# MICRO_SQUARED_SENSING_MCP1700.net
KiCad netlist of a schematic drawn in EAGLE
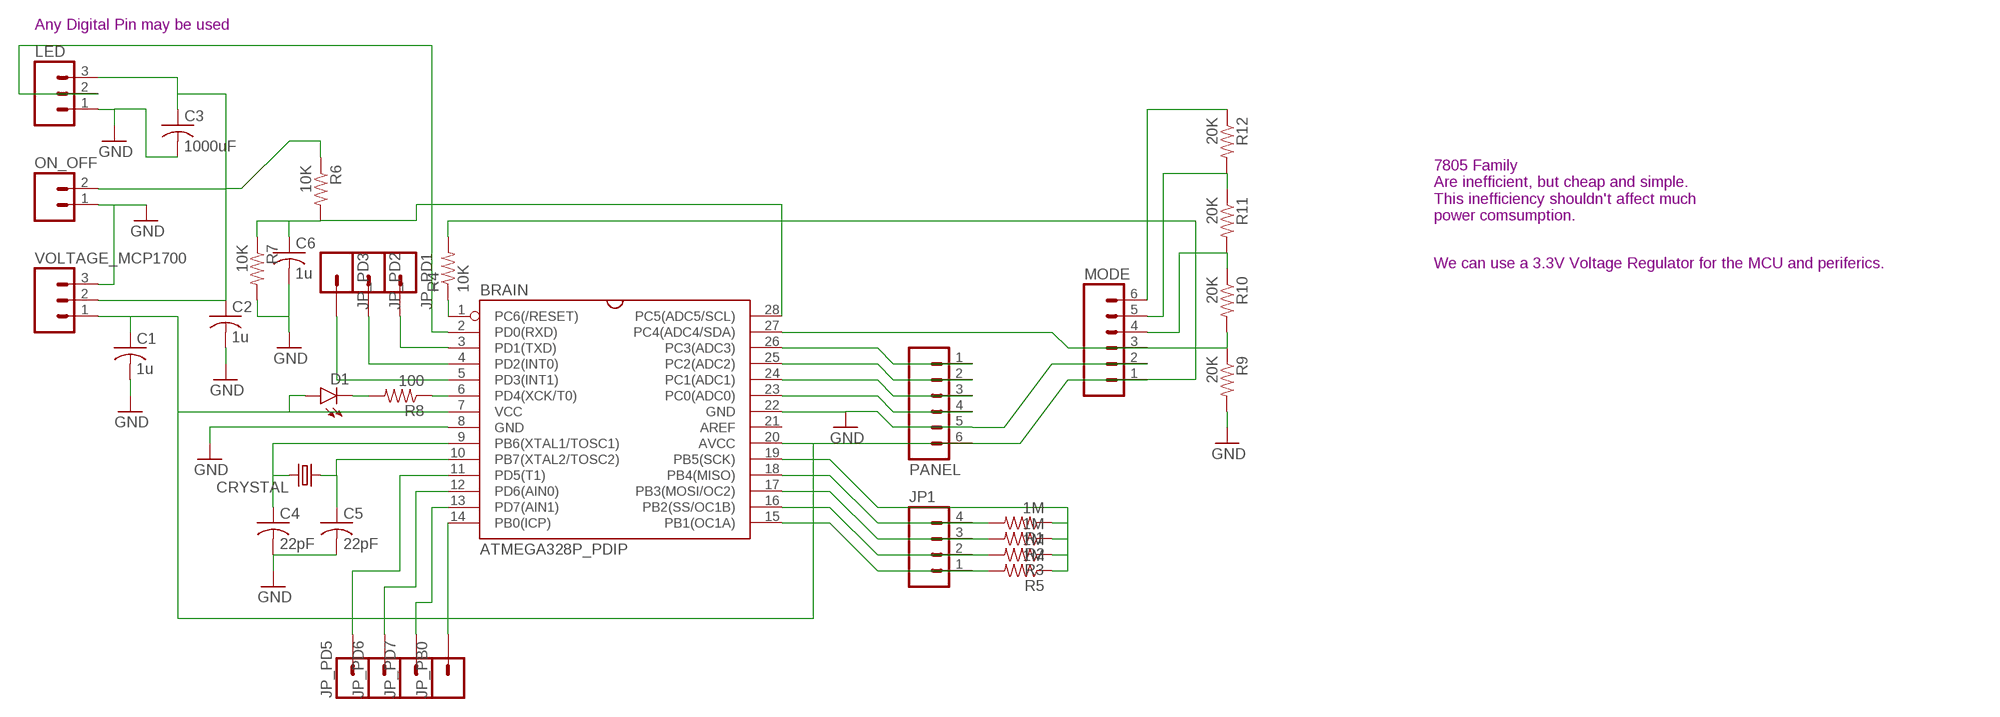
[diagram p0: schematic, sheet 1]

(export (version "E")
  (design (tool "Eeschema 10.0.6"))
  (components
    (comp (ref "BRAIN")
      (value "ATMEGA328P_PDIP")
      (footprint "eagle-import:DIL-28-3")
      (libsource (lib "eagle-import") (part "ATMEGA328P_PDIP"))
    )
    (comp (ref "C1")
      (value "1u")
      (footprint "eagle-import:C050-025X075")
      (libsource (lib "eagle-import") (part "C-US050-025X075"))
    )
    (comp (ref "C2")
      (value "1u")
      (footprint "eagle-import:C050-025X075")
      (libsource (lib "eagle-import") (part "C-US050-025X075"))
    )
    (comp (ref "C3")
      (value "1000uF")
      (footprint "eagle-import:C050-075X075")
      (libsource (lib "eagle-import") (part "C-US050-075X075"))
    )
    (comp (ref "C4")
      (value "22pF")
      (footprint "eagle-import:C025-024X044")
      (libsource (lib "eagle-import") (part "C-US025-024X044"))
    )
    (comp (ref "C5")
      (value "22pF")
      (footprint "eagle-import:C025-024X044")
      (libsource (lib "eagle-import") (part "C-US025-024X044"))
    )
    (comp (ref "C6")
      (value "1u")
      (footprint "eagle-import:C050-025X075")
      (libsource (lib "eagle-import") (part "C-US050-025X075"))
    )
    (comp (ref "CRYSTAL")
      (value "CRYSTALHC49US")
      (footprint "eagle-import:HC49US")
      (libsource (lib "eagle-import") (part "CRYSTALHC49US"))
    )
    (comp (ref "D1")
      (value "LED3MM")
      (footprint "eagle-import:LED3MM")
      (libsource (lib "eagle-import") (part "LED3MM"))
    )
    (comp (ref "JP1")
      (value "M04PTH")
      (footprint "eagle-import:1X04")
      (libsource (lib "eagle-import") (part "M04PTH"))
    )
    (comp (ref "JP_PB0")
      (value "M01PTH")
      (footprint "eagle-import:1X01")
      (libsource (lib "eagle-import") (part "M01PTH"))
    )
    (comp (ref "JP_PD1")
      (value "M01PTH")
      (footprint "eagle-import:1X01")
      (libsource (lib "eagle-import") (part "M01PTH"))
    )
    (comp (ref "JP_PD2")
      (value "M01PTH")
      (footprint "eagle-import:1X01")
      (libsource (lib "eagle-import") (part "M01PTH"))
    )
    (comp (ref "JP_PD3")
      (value "M01PTH")
      (footprint "eagle-import:1X01")
      (libsource (lib "eagle-import") (part "M01PTH"))
    )
    (comp (ref "JP_PD5")
      (value "M01PTH")
      (footprint "eagle-import:1X01")
      (libsource (lib "eagle-import") (part "M01PTH"))
    )
    (comp (ref "JP_PD6")
      (value "M01PTH")
      (footprint "eagle-import:1X01")
      (libsource (lib "eagle-import") (part "M01PTH"))
    )
    (comp (ref "JP_PD7")
      (value "M01PTH")
      (footprint "eagle-import:1X01")
      (libsource (lib "eagle-import") (part "M01PTH"))
    )
    (comp (ref "LED")
      (value "M03PTH")
      (footprint "eagle-import:1X03")
      (libsource (lib "eagle-import") (part "M03PTH"))
    )
    (comp (ref "MODE")
      (value "M06SILK_FEMALE_PTH")
      (footprint "eagle-import:1X06")
      (libsource (lib "eagle-import") (part "M06SILK_FEMALE_PTH"))
    )
    (comp (ref "ON_OFF")
      (value "M02PTH")
      (footprint "eagle-import:1X02")
      (libsource (lib "eagle-import") (part "M02PTH"))
    )
    (comp (ref "PANEL")
      (value "M06NO_SILK_FEMALE_PTH")
      (footprint "eagle-import:1X06_NO_SILK")
      (libsource (lib "eagle-import") (part "M06NO_SILK_FEMALE_PTH"))
    )
    (comp (ref "R1")
      (value "1M")
      (footprint "eagle-import:AXIAL-0.3")
      (libsource (lib "eagle-import") (part "RESISTORAXIAL-0.3"))
    )
    (comp (ref "R2")
      (value "1M")
      (footprint "eagle-import:AXIAL-0.3")
      (libsource (lib "eagle-import") (part "RESISTORAXIAL-0.3"))
    )
    (comp (ref "R3")
      (value "1M")
      (footprint "eagle-import:AXIAL-0.3")
      (libsource (lib "eagle-import") (part "RESISTORAXIAL-0.3"))
    )
    (comp (ref "R4")
      (value "10K")
      (footprint "eagle-import:AXIAL-0.3")
      (libsource (lib "eagle-import") (part "RESISTORAXIAL-0.3"))
    )
    (comp (ref "R5")
      (value "1M")
      (footprint "eagle-import:AXIAL-0.3")
      (libsource (lib "eagle-import") (part "RESISTORAXIAL-0.3"))
    )
    (comp (ref "R6")
      (value "10K")
      (footprint "eagle-import:AXIAL-0.3")
      (libsource (lib "eagle-import") (part "RESISTORAXIAL-0.3"))
    )
    (comp (ref "R7")
      (value "10K")
      (footprint "eagle-import:AXIAL-0.3")
      (libsource (lib "eagle-import") (part "RESISTORAXIAL-0.3"))
    )
    (comp (ref "R8")
      (value "100")
      (footprint "eagle-import:AXIAL-0.3")
      (libsource (lib "eagle-import") (part "RESISTORAXIAL-0.3"))
    )
    (comp (ref "R9")
      (value "20K")
      (footprint "eagle-import:AXIAL-0.3")
      (libsource (lib "eagle-import") (part "RESISTORAXIAL-0.3"))
    )
    (comp (ref "R10")
      (value "20K")
      (footprint "eagle-import:AXIAL-0.3")
      (libsource (lib "eagle-import") (part "RESISTORAXIAL-0.3"))
    )
    (comp (ref "R11")
      (value "20K")
      (footprint "eagle-import:AXIAL-0.3")
      (libsource (lib "eagle-import") (part "RESISTORAXIAL-0.3"))
    )
    (comp (ref "R12")
      (value "20K")
      (footprint "eagle-import:AXIAL-0.3")
      (libsource (lib "eagle-import") (part "RESISTORAXIAL-0.3"))
    )
    (comp (ref "VOLTAGE_MCP1700")
      (value "M03PTH")
      (footprint "eagle-import:1X03")
      (libsource (lib "eagle-import") (part "M03PTH"))
    )
  )
  (nets
    (net (code "1") (name "GND") (class "Default")
      (node (ref "BRAIN") (pin "22") (pinfunction "GND_22") (pintype "bidirectional"))
      (node (ref "BRAIN") (pin "8") (pinfunction "GND_8") (pintype "bidirectional"))
      (node (ref "C1") (pin "2") (pinfunction "2_2") (pintype "passive"))
      (node (ref "C2") (pin "2") (pinfunction "2_2") (pintype "passive"))
      (node (ref "C3") (pin "2") (pinfunction "2_2") (pintype "passive"))
      (node (ref "C4") (pin "2") (pinfunction "2_2") (pintype "passive"))
      (node (ref "C5") (pin "2") (pinfunction "2_2") (pintype "passive"))
      (node (ref "C6") (pin "2") (pinfunction "2_2") (pintype "passive"))
      (node (ref "LED") (pin "1") (pinfunction "1_1") (pintype "passive"))
      (node (ref "MODE") (pin "2") (pinfunction "2_2") (pintype "passive"))
      (node (ref "ON_OFF") (pin "1") (pinfunction "1_1") (pintype "passive"))
      (node (ref "PANEL") (pin "5") (pinfunction "5_5") (pintype "passive"))
      (node (ref "R7") (pin "P$2") (pinfunction "2_P$2") (pintype "passive"))
      (node (ref "R9") (pin "P$2") (pinfunction "2_P$2") (pintype "passive"))
      (node (ref "VOLTAGE_MCP1700") (pin "3") (pinfunction "3_3") (pintype "passive"))
    )
    (net (code "2") (name "Net-(BRAIN-AVCC)") (class "Default")
      (node (ref "BRAIN") (pin "20") (pinfunction "AVCC_20") (pintype "bidirectional"))
      (node (ref "BRAIN") (pin "7") (pinfunction "VCC_7") (pintype "bidirectional"))
      (node (ref "C1") (pin "1") (pinfunction "1_1") (pintype "passive"))
      (node (ref "D1") (pin "A") (pinfunction "A_A") (pintype "passive"))
      (node (ref "MODE") (pin "1") (pinfunction "1_1") (pintype "passive"))
      (node (ref "PANEL") (pin "6") (pinfunction "6_6") (pintype "passive"))
      (node (ref "R4") (pin "P$2") (pinfunction "2_P$2") (pintype "passive"))
      (node (ref "VOLTAGE_MCP1700") (pin "1") (pinfunction "1_1") (pintype "passive"))
    )
    (net (code "3") (name "Net-(BRAIN-PB0(ICP))") (class "Default")
      (node (ref "BRAIN") (pin "14") (pinfunction "PB0(ICP)_14") (pintype "bidirectional"))
      (node (ref "JP_PB0") (pin "1") (pinfunction "1_1") (pintype "passive"))
    )
    (net (code "4") (name "Net-(BRAIN-PB1(OC1A))") (class "Default")
      (node (ref "BRAIN") (pin "15") (pinfunction "PB1(OC1A)_15") (pintype "bidirectional"))
      (node (ref "JP1") (pin "1") (pinfunction "1_1") (pintype "passive"))
      (node (ref "R5") (pin "P$2") (pinfunction "2_P$2") (pintype "passive"))
    )
    (net (code "5") (name "Net-(BRAIN-PB2(SS{slash}OC1B))") (class "Default")
      (node (ref "BRAIN") (pin "16") (pinfunction "PB2(SS/OC1B)_16") (pintype "bidirectional"))
      (node (ref "JP1") (pin "2") (pinfunction "2_2") (pintype "passive"))
      (node (ref "R3") (pin "P$2") (pinfunction "2_P$2") (pintype "passive"))
    )
    (net (code "6") (name "Net-(BRAIN-PB3(MOSI{slash}OC2))") (class "Default")
      (node (ref "BRAIN") (pin "17") (pinfunction "PB3(MOSI/OC2)_17") (pintype "bidirectional"))
      (node (ref "JP1") (pin "3") (pinfunction "3_3") (pintype "passive"))
      (node (ref "R2") (pin "P$2") (pinfunction "2_P$2") (pintype "passive"))
    )
    (net (code "7") (name "Net-(BRAIN-PB4(MISO))") (class "Default")
      (node (ref "BRAIN") (pin "18") (pinfunction "PB4(MISO)_18") (pintype "bidirectional"))
      (node (ref "JP1") (pin "4") (pinfunction "4_4") (pintype "passive"))
      (node (ref "R1") (pin "P$2") (pinfunction "2_P$2") (pintype "passive"))
    )
    (net (code "8") (name "Net-(BRAIN-PB5(SCK))") (class "Default")
      (node (ref "BRAIN") (pin "19") (pinfunction "PB5(SCK)_19") (pintype "bidirectional"))
      (node (ref "R1") (pin "P$1") (pinfunction "1_P$1") (pintype "passive"))
      (node (ref "R2") (pin "P$1") (pinfunction "1_P$1") (pintype "passive"))
      (node (ref "R3") (pin "P$1") (pinfunction "1_P$1") (pintype "passive"))
      (node (ref "R5") (pin "P$1") (pinfunction "1_P$1") (pintype "passive"))
    )
    (net (code "9") (name "Net-(BRAIN-PB6(XTAL1{slash}TOSC1))") (class "Default")
      (node (ref "BRAIN") (pin "9") (pinfunction "PB6(XTAL1/TOSC1)_9") (pintype "bidirectional"))
      (node (ref "C4") (pin "1") (pinfunction "1_1") (pintype "passive"))
      (node (ref "CRYSTAL") (pin "2") (pinfunction "2_2") (pintype "passive"))
    )
    (net (code "10") (name "Net-(BRAIN-PB7(XTAL2{slash}TOSC2))") (class "Default")
      (node (ref "BRAIN") (pin "10") (pinfunction "PB7(XTAL2/TOSC2)_10") (pintype "bidirectional"))
      (node (ref "C5") (pin "1") (pinfunction "1_1") (pintype "passive"))
      (node (ref "CRYSTAL") (pin "1") (pinfunction "1_1") (pintype "passive"))
    )
    (net (code "11") (name "Net-(BRAIN-PC0(ADC0))") (class "Default")
      (node (ref "BRAIN") (pin "23") (pinfunction "PC0(ADC0)_23") (pintype "bidirectional"))
      (node (ref "PANEL") (pin "4") (pinfunction "4_4") (pintype "passive"))
    )
    (net (code "12") (name "Net-(BRAIN-PC1(ADC1))") (class "Default")
      (node (ref "BRAIN") (pin "24") (pinfunction "PC1(ADC1)_24") (pintype "bidirectional"))
      (node (ref "PANEL") (pin "3") (pinfunction "3_3") (pintype "passive"))
    )
    (net (code "13") (name "Net-(BRAIN-PC2(ADC2))") (class "Default")
      (node (ref "BRAIN") (pin "25") (pinfunction "PC2(ADC2)_25") (pintype "bidirectional"))
      (node (ref "PANEL") (pin "2") (pinfunction "2_2") (pintype "passive"))
    )
    (net (code "14") (name "Net-(BRAIN-PC3(ADC3))") (class "Default")
      (node (ref "BRAIN") (pin "26") (pinfunction "PC3(ADC3)_26") (pintype "bidirectional"))
      (node (ref "PANEL") (pin "1") (pinfunction "1_1") (pintype "passive"))
    )
    (net (code "15") (name "Net-(BRAIN-PC4(ADC4{slash}SDA))") (class "Default")
      (node (ref "BRAIN") (pin "27") (pinfunction "PC4(ADC4/SDA)_27") (pintype "bidirectional"))
      (node (ref "MODE") (pin "3") (pinfunction "3_3") (pintype "passive"))
      (node (ref "R10") (pin "P$2") (pinfunction "2_P$2") (pintype "passive"))
      (node (ref "R9") (pin "P$1") (pinfunction "1_P$1") (pintype "passive"))
    )
    (net (code "16") (name "Net-(BRAIN-PC5(ADC5{slash}SCL))") (class "Default")
      (node (ref "BRAIN") (pin "28") (pinfunction "PC5(ADC5/SCL)_28") (pintype "bidirectional"))
      (node (ref "C6") (pin "1") (pinfunction "1_1") (pintype "passive"))
      (node (ref "R6") (pin "P$2") (pinfunction "2_P$2") (pintype "passive"))
      (node (ref "R7") (pin "P$1") (pinfunction "1_P$1") (pintype "passive"))
    )
    (net (code "17") (name "Net-(BRAIN-PC6({slash}RESET))") (class "Default")
      (node (ref "BRAIN") (pin "1") (pinfunction "PC6(/RESET)_1") (pintype "bidirectional"))
      (node (ref "R4") (pin "P$1") (pinfunction "1_P$1") (pintype "passive"))
    )
    (net (code "18") (name "Net-(BRAIN-PD0(RXD))") (class "Default")
      (node (ref "BRAIN") (pin "2") (pinfunction "PD0(RXD)_2") (pintype "bidirectional"))
      (node (ref "LED") (pin "2") (pinfunction "2_2") (pintype "passive"))
    )
    (net (code "19") (name "Net-(BRAIN-PD1(TXD))") (class "Default")
      (node (ref "BRAIN") (pin "3") (pinfunction "PD1(TXD)_3") (pintype "bidirectional"))
      (node (ref "JP_PD1") (pin "1") (pinfunction "1_1") (pintype "passive"))
    )
    (net (code "20") (name "Net-(BRAIN-PD2(INT0))") (class "Default")
      (node (ref "BRAIN") (pin "4") (pinfunction "PD2(INT0)_4") (pintype "bidirectional"))
      (node (ref "JP_PD2") (pin "1") (pinfunction "1_1") (pintype "passive"))
    )
    (net (code "21") (name "Net-(BRAIN-PD3(INT1))") (class "Default")
      (node (ref "BRAIN") (pin "5") (pinfunction "PD3(INT1)_5") (pintype "bidirectional"))
      (node (ref "JP_PD3") (pin "1") (pinfunction "1_1") (pintype "passive"))
    )
    (net (code "22") (name "Net-(BRAIN-PD4(XCK{slash}T0))") (class "Default")
      (node (ref "BRAIN") (pin "6") (pinfunction "PD4(XCK/T0)_6") (pintype "bidirectional"))
      (node (ref "R8") (pin "P$1") (pinfunction "1_P$1") (pintype "passive"))
    )
    (net (code "23") (name "Net-(BRAIN-PD5(T1))") (class "Default")
      (node (ref "BRAIN") (pin "11") (pinfunction "PD5(T1)_11") (pintype "bidirectional"))
      (node (ref "JP_PD5") (pin "1") (pinfunction "1_1") (pintype "passive"))
    )
    (net (code "24") (name "Net-(BRAIN-PD6(AIN0))") (class "Default")
      (node (ref "BRAIN") (pin "12") (pinfunction "PD6(AIN0)_12") (pintype "bidirectional"))
      (node (ref "JP_PD6") (pin "1") (pinfunction "1_1") (pintype "passive"))
    )
    (net (code "25") (name "Net-(BRAIN-PD7(AIN1))") (class "Default")
      (node (ref "BRAIN") (pin "13") (pinfunction "PD7(AIN1)_13") (pintype "bidirectional"))
      (node (ref "JP_PD7") (pin "1") (pinfunction "1_1") (pintype "passive"))
    )
    (net (code "26") (name "Net-(D1-C)") (class "Default")
      (node (ref "D1") (pin "K") (pinfunction "C_K") (pintype "passive"))
      (node (ref "R8") (pin "P$2") (pinfunction "2_P$2") (pintype "passive"))
    )
    (net (code "27") (name "Net-(R6-1)") (class "Default")
      (node (ref "C2") (pin "1") (pinfunction "1_1") (pintype "passive"))
      (node (ref "C3") (pin "1") (pinfunction "1_1") (pintype "passive"))
      (node (ref "LED") (pin "3") (pinfunction "3_3") (pintype "passive"))
      (node (ref "ON_OFF") (pin "2") (pinfunction "2_2") (pintype "passive"))
      (node (ref "R6") (pin "P$1") (pinfunction "1_P$1") (pintype "passive"))
      (node (ref "VOLTAGE_MCP1700") (pin "2") (pinfunction "2_2") (pintype "passive"))
    )
    (net (code "28") (name "Net-(R10-1)") (class "Default")
      (node (ref "MODE") (pin "4") (pinfunction "4_4") (pintype "passive"))
      (node (ref "R10") (pin "P$1") (pinfunction "1_P$1") (pintype "passive"))
      (node (ref "R11") (pin "P$2") (pinfunction "2_P$2") (pintype "passive"))
    )
    (net (code "29") (name "Net-(R11-1)") (class "Default")
      (node (ref "MODE") (pin "5") (pinfunction "5_5") (pintype "passive"))
      (node (ref "R11") (pin "P$1") (pinfunction "1_P$1") (pintype "passive"))
      (node (ref "R12") (pin "P$2") (pinfunction "2_P$2") (pintype "passive"))
    )
    (net (code "30") (name "Net-(R12-1)") (class "Default")
      (node (ref "MODE") (pin "6") (pinfunction "6_6") (pintype "passive"))
      (node (ref "R12") (pin "P$1") (pinfunction "1_P$1") (pintype "passive"))
    )
    (net (code "31") (name "unconnected-(BRAIN-AREF-Pad21)") (class "Default")
      (node (ref "BRAIN") (pin "21") (pinfunction "AREF_21") (pintype "bidirectional"))
    )
  )
)
